# lightmeter_proto3.net
KiCad netlist of a schematic drawn in EAGLE
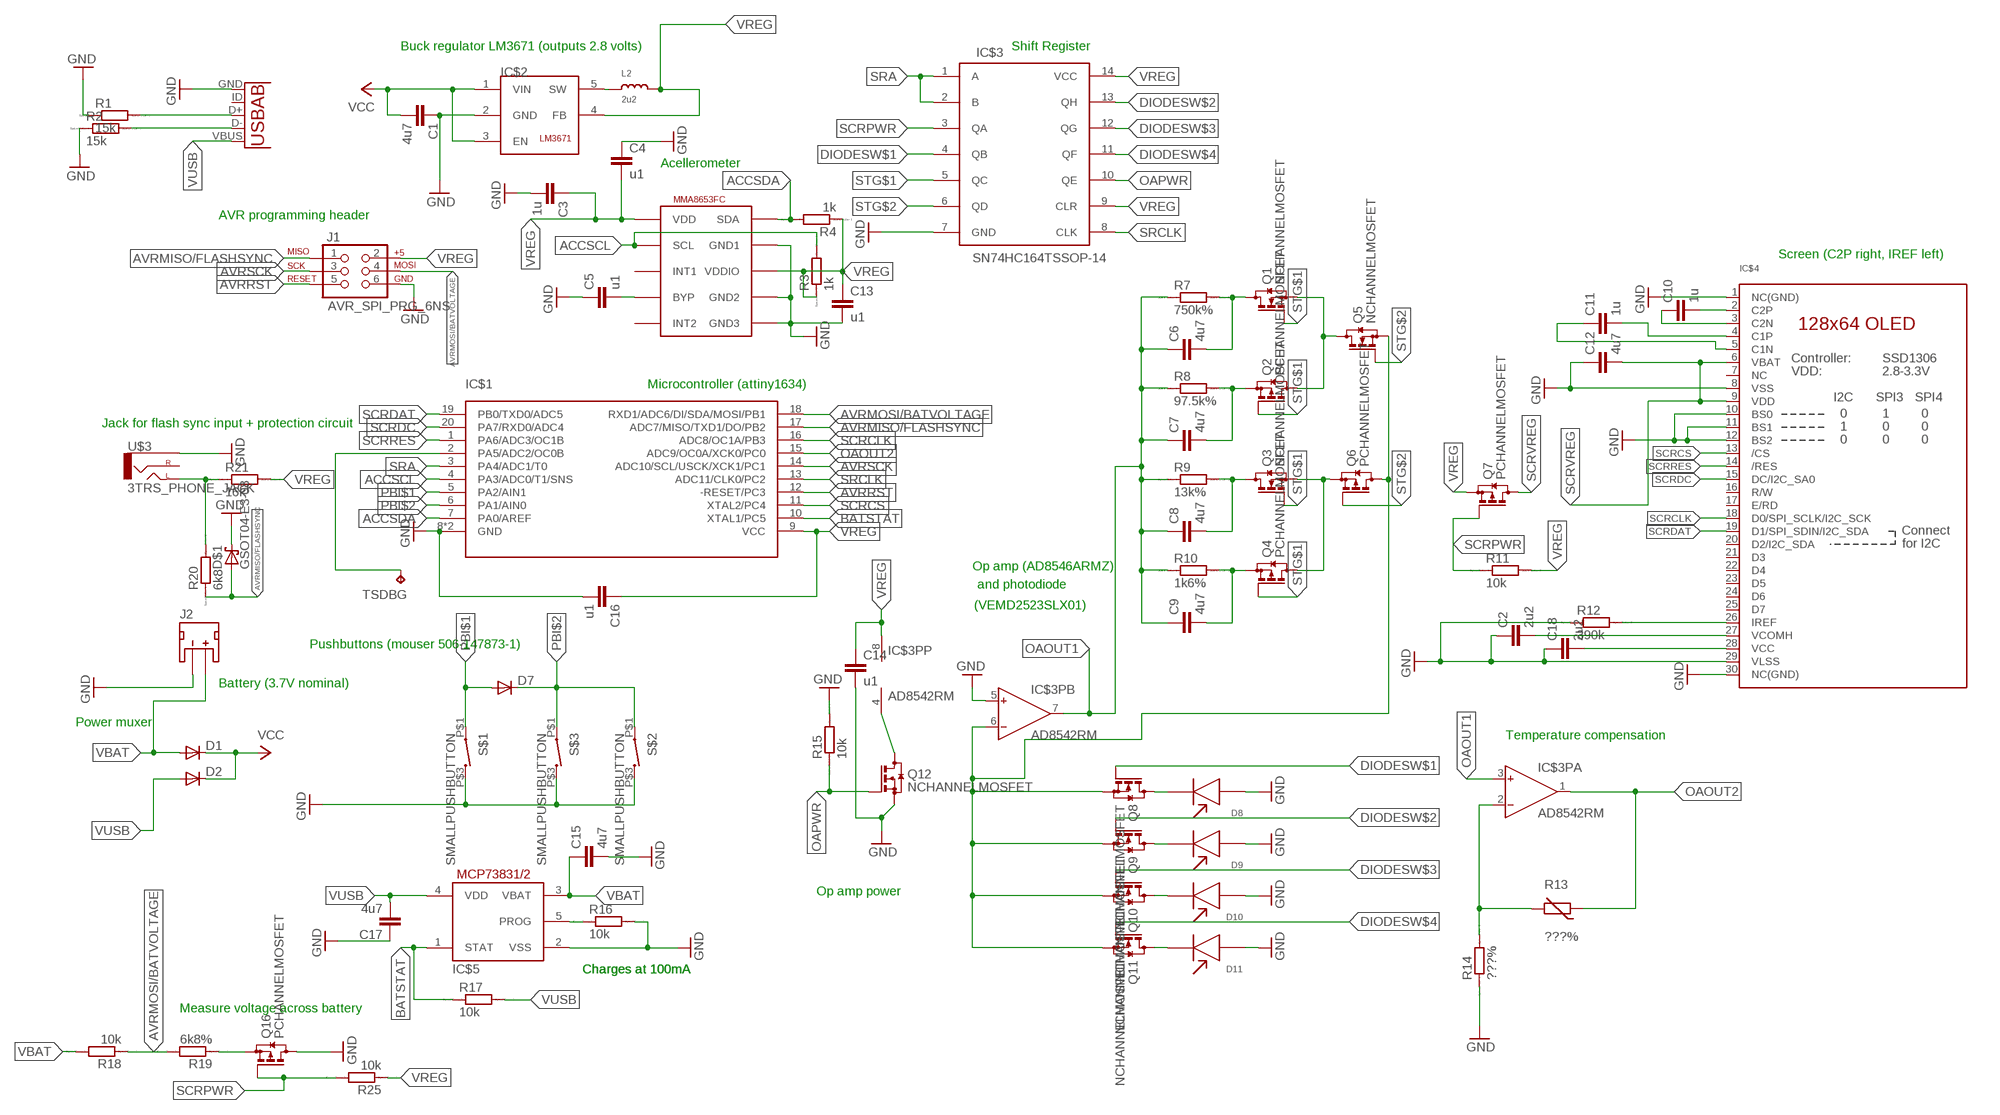
[diagram p0: schematic, sheet 1]

(export (version "E")
  (design (tool "Eeschema 10.0.6"))
  (components
    (comp (ref "C1")
      (value "4u7")
      (footprint "eagle-import:C0402")
      (libsource (lib "eagle-import") (part "C-EUC0402"))
    )
    (comp (ref "C2")
      (value "2u2")
      (footprint "eagle-import:C0402")
      (libsource (lib "eagle-import") (part "C-EUC0402"))
    )
    (comp (ref "C3")
      (value "1u")
      (footprint "eagle-import:C0402")
      (libsource (lib "eagle-import") (part "C-EUC0402"))
    )
    (comp (ref "C4")
      (value "u1")
      (footprint "eagle-import:C0402")
      (libsource (lib "eagle-import") (part "C-EUC0402"))
    )
    (comp (ref "C5")
      (value "u1")
      (footprint "eagle-import:C0402")
      (libsource (lib "eagle-import") (part "C-EUC0402"))
    )
    (comp (ref "C6")
      (value "4u7")
      (footprint "eagle-import:C0402")
      (libsource (lib "eagle-import") (part "C-EUC0402"))
    )
    (comp (ref "C7")
      (value "4u7")
      (footprint "eagle-import:C0402")
      (libsource (lib "eagle-import") (part "C-EUC0402"))
    )
    (comp (ref "C8")
      (value "4u7")
      (footprint "eagle-import:C0402")
      (libsource (lib "eagle-import") (part "C-EUC0402"))
    )
    (comp (ref "C9")
      (value "4u7")
      (footprint "eagle-import:C0402")
      (libsource (lib "eagle-import") (part "C-EUC0402"))
    )
    (comp (ref "C10")
      (value "1u")
      (footprint "eagle-import:C0402")
      (libsource (lib "eagle-import") (part "C-EUC0402"))
    )
    (comp (ref "C11")
      (value "1u")
      (footprint "eagle-import:C0402")
      (libsource (lib "eagle-import") (part "C-EUC0402"))
    )
    (comp (ref "C12")
      (value "4u7")
      (footprint "eagle-import:C0402")
      (libsource (lib "eagle-import") (part "C-EUC0402"))
    )
    (comp (ref "C13")
      (value "u1")
      (footprint "eagle-import:C0402")
      (libsource (lib "eagle-import") (part "C-EUC0402"))
    )
    (comp (ref "C14")
      (value "u1")
      (footprint "eagle-import:C0402")
      (libsource (lib "eagle-import") (part "C-EUC0402"))
    )
    (comp (ref "C15")
      (value "4u7")
      (footprint "eagle-import:C0402")
      (libsource (lib "eagle-import") (part "C-EUC0402"))
    )
    (comp (ref "C16")
      (value "u1")
      (footprint "eagle-import:C0402")
      (libsource (lib "eagle-import") (part "C-EUC0402"))
    )
    (comp (ref "C17")
      (value "4u7")
      (footprint "eagle-import:C0402")
      (libsource (lib "eagle-import") (part "C-EUC0402"))
    )
    (comp (ref "C18")
      (value "2u2")
      (footprint "eagle-import:C0402")
      (libsource (lib "eagle-import") (part "C-EUC0402"))
    )
    (comp (ref "D$1")
      (value "GSOT04-E3-08")
      (footprint "eagle-import:SOT23")
      (libsource (lib "eagle-import") (part "GSOT04-E3-08"))
    )
    (comp (ref "D1")
      (value "DIODE-SOD323-W")
      (footprint "eagle-import:SOD323-W")
      (libsource (lib "eagle-import") (part "DIODE-SOD323-W"))
    )
    (comp (ref "D2")
      (value "DIODE-SOD323-W")
      (footprint "eagle-import:SOD323-W")
      (libsource (lib "eagle-import") (part "DIODE-SOD323-W"))
    )
    (comp (ref "D7")
      (value "DIODE-SOD323-W")
      (footprint "eagle-import:SOD323-W")
      (libsource (lib "eagle-import") (part "DIODE-SOD323-W"))
    )
    (comp (ref "D8")
      (value "VEMD2523SLX01")
      (footprint "eagle-import:VEMD2523SLX01")
      (libsource (lib "eagle-import") (part "VEMD2523SLX01"))
    )
    (comp (ref "D9")
      (value "VEMD2523SLX01")
      (footprint "eagle-import:VEMD2523SLX01")
      (libsource (lib "eagle-import") (part "VEMD2523SLX01"))
    )
    (comp (ref "D10")
      (value "VEMD2523SLX01")
      (footprint "eagle-import:VEMD2523SLX01")
      (libsource (lib "eagle-import") (part "VEMD2523SLX01"))
    )
    (comp (ref "D11")
      (value "VEMD2523SLX01")
      (footprint "eagle-import:VEMD2523SLX01")
      (libsource (lib "eagle-import") (part "VEMD2523SLX01"))
    )
    (comp (ref "IC$1")
      (value "ATTINY1634MLF20")
      (footprint "eagle-import:MLF20")
      (libsource (lib "eagle-import") (part "ATTINY1634MLF20"))
    )
    (comp (ref "IC$2")
      (value "LM3671")
      (footprint "eagle-import:SOT23-5")
      (libsource (lib "eagle-import") (part "LM3671"))
    )
    (comp (ref "IC$3")
      (value "SN74HC164TSSOP-14")
      (footprint "eagle-import:TSSOP14")
      (libsource (lib "eagle-import") (part "SN74HC164TSSOP-14"))
    )
    (comp (ref "IC$3P")
      (value "AD8542RM")
      (footprint "eagle-import:MSOP08")
      (fields (field (name "MPN") "AD8542ARZ"))
      (libsource (lib "eagle-import") (part "AD8542RM"))
    )
    (comp (ref "IC$4")
      (value "DISP_OLED_UG-2864HSWEG010.96\"")
      (footprint "eagle-import:UG-2864HSWEG01_0.96IN_WRAPAROUND")
      (libsource (lib "eagle-import") (part "DISP_OLED_UG-2864HSWEG010.96{dblquote}"))
    )
    (comp (ref "IC$5")
      (value "MCP73831/OT")
      (footprint "eagle-import:SOT23-5L")
      (libsource (lib "eagle-import") (part "MCP73831/OT"))
    )
    (comp (ref "IC$6")
      (value "MMA8653")
      (footprint "eagle-import:DFN-10")
      (libsource (lib "eagle-import") (part "MMA8653"))
    )
    (comp (ref "J1")
      (value "AVR_SPI_PRG_6NS")
      (footprint "eagle-import:2X3-NS")
      (libsource (lib "eagle-import") (part "AVR_SPI_PRG_6NS"))
    )
    (comp (ref "J2")
      (value "JST_2MM_MALE")
      (footprint "eagle-import:JST-2-SMD")
      (libsource (lib "eagle-import") (part "JST_2MM_MALE"))
    )
    (comp (ref "L2")
      (value "2u2")
      (footprint "eagle-import:_0603")
      (libsource (lib "eagle-import") (part "INDUCTOR_0603"))
    )
    (comp (ref "Q1")
      (value "NCHANNELMOSFET")
      (footprint "eagle-import:SOT-416-3")
      (libsource (lib "eagle-import") (part "NCHANNELMOSFET"))
    )
    (comp (ref "Q2")
      (value "PCHANNELMOSFET")
      (footprint "eagle-import:SOT-416-3")
      (libsource (lib "eagle-import") (part "PCHANNELMOSFET"))
    )
    (comp (ref "Q3")
      (value "NCHANNELMOSFET")
      (footprint "eagle-import:SOT-416-3")
      (libsource (lib "eagle-import") (part "NCHANNELMOSFET"))
    )
    (comp (ref "Q4")
      (value "PCHANNELMOSFET")
      (footprint "eagle-import:SOT-416-3")
      (libsource (lib "eagle-import") (part "PCHANNELMOSFET"))
    )
    (comp (ref "Q5")
      (value "NCHANNELMOSFET")
      (footprint "eagle-import:SOT-416-3")
      (libsource (lib "eagle-import") (part "NCHANNELMOSFET"))
    )
    (comp (ref "Q6")
      (value "PCHANNELMOSFET")
      (footprint "eagle-import:SOT-416-3")
      (libsource (lib "eagle-import") (part "PCHANNELMOSFET"))
    )
    (comp (ref "Q7")
      (value "PCHANNELMOSFET")
      (footprint "eagle-import:SOT-416-3")
      (libsource (lib "eagle-import") (part "PCHANNELMOSFET"))
    )
    (comp (ref "Q8")
      (value "NCHANNELMOSFET")
      (footprint "eagle-import:SOT-416-3")
      (libsource (lib "eagle-import") (part "NCHANNELMOSFET"))
    )
    (comp (ref "Q9")
      (value "NCHANNELMOSFET")
      (footprint "eagle-import:SOT-416-3")
      (libsource (lib "eagle-import") (part "NCHANNELMOSFET"))
    )
    (comp (ref "Q10")
      (value "NCHANNELMOSFET")
      (footprint "eagle-import:SOT-416-3")
      (libsource (lib "eagle-import") (part "NCHANNELMOSFET"))
    )
    (comp (ref "Q11")
      (value "NCHANNELMOSFET")
      (footprint "eagle-import:SOT-416-3")
      (libsource (lib "eagle-import") (part "NCHANNELMOSFET"))
    )
    (comp (ref "Q12")
      (value "NCHANNELMOSFET")
      (footprint "eagle-import:SOT-416-3")
      (libsource (lib "eagle-import") (part "NCHANNELMOSFET"))
    )
    (comp (ref "Q16")
      (value "PCHANNELMOSFET")
      (footprint "eagle-import:SOT-416-3")
      (libsource (lib "eagle-import") (part "PCHANNELMOSFET"))
    )
    (comp (ref "R1")
      (value "15k")
      (footprint "eagle-import:R0402")
      (libsource (lib "eagle-import") (part "R-EU_R0402"))
    )
    (comp (ref "R2")
      (value "15k")
      (footprint "eagle-import:R0402")
      (libsource (lib "eagle-import") (part "R-EU_R0402"))
    )
    (comp (ref "R3")
      (value "1k")
      (footprint "eagle-import:R0402")
      (libsource (lib "eagle-import") (part "R-EU_R0402"))
    )
    (comp (ref "R4")
      (value "1k")
      (footprint "eagle-import:R0402")
      (libsource (lib "eagle-import") (part "R-EU_R0402"))
    )
    (comp (ref "R7")
      (value "750k%")
      (footprint "eagle-import:R0402")
      (libsource (lib "eagle-import") (part "R-EU_R0402"))
    )
    (comp (ref "R8")
      (value "97.5k%")
      (footprint "eagle-import:R0402")
      (libsource (lib "eagle-import") (part "R-EU_R0402"))
    )
    (comp (ref "R9")
      (value "13k%")
      (footprint "eagle-import:R0402")
      (libsource (lib "eagle-import") (part "R-EU_R0402"))
    )
    (comp (ref "R10")
      (value "1k6%")
      (footprint "eagle-import:R0402")
      (libsource (lib "eagle-import") (part "R-EU_R0402"))
    )
    (comp (ref "R11")
      (value "10k")
      (footprint "eagle-import:R0402")
      (libsource (lib "eagle-import") (part "R-EU_R0402"))
    )
    (comp (ref "R12")
      (value "390k")
      (footprint "eagle-import:R0402")
      (libsource (lib "eagle-import") (part "R-EU_R0402"))
    )
    (comp (ref "R13")
      (value "???%")
      (footprint "eagle-import:R0402")
      (libsource (lib "eagle-import") (part "THERMISTORR0402"))
    )
    (comp (ref "R14")
      (value "???%")
      (footprint "eagle-import:R0402")
      (libsource (lib "eagle-import") (part "R-EU_R0402"))
    )
    (comp (ref "R15")
      (value "10k")
      (footprint "eagle-import:R0402")
      (libsource (lib "eagle-import") (part "R-EU_R0402"))
    )
    (comp (ref "R16")
      (value "10k")
      (footprint "eagle-import:R0402")
      (libsource (lib "eagle-import") (part "R-EU_R0402"))
    )
    (comp (ref "R17")
      (value "10k")
      (footprint "eagle-import:R0402")
      (libsource (lib "eagle-import") (part "R-EU_R0402"))
    )
    (comp (ref "R18")
      (value "10k")
      (footprint "eagle-import:R0402")
      (libsource (lib "eagle-import") (part "R-EU_R0402"))
    )
    (comp (ref "R19")
      (value "6k8%")
      (footprint "eagle-import:R0402")
      (libsource (lib "eagle-import") (part "R-EU_R0402"))
    )
    (comp (ref "R20")
      (value "6k8")
      (footprint "eagle-import:R0402")
      (libsource (lib "eagle-import") (part "R-EU_R0402"))
    )
    (comp (ref "R21")
      (value "16k")
      (footprint "eagle-import:R0402")
      (libsource (lib "eagle-import") (part "R-EU_R0402"))
    )
    (comp (ref "R25")
      (value "10k")
      (footprint "eagle-import:R0402")
      (libsource (lib "eagle-import") (part "R-EU_R0402"))
    )
    (comp (ref "S$1")
      (value "SMALLPUSHBUTTON")
      (footprint "eagle-import:BUTTON")
      (libsource (lib "eagle-import") (part "SMALLPUSHBUTTON"))
    )
    (comp (ref "S$2")
      (value "SMALLPUSHBUTTON")
      (footprint "eagle-import:BUTTON")
      (libsource (lib "eagle-import") (part "SMALLPUSHBUTTON"))
    )
    (comp (ref "S$3")
      (value "SMALLPUSHBUTTON")
      (footprint "eagle-import:BUTTON")
      (libsource (lib "eagle-import") (part "SMALLPUSHBUTTON"))
    )
    (comp (ref "TSDBG")
      (value "TPPAD1-13")
      (footprint "eagle-import:P1-13")
      (libsource (lib "eagle-import") (part "TPPAD1-13"))
    )
    (comp (ref "U$3")
      (value "3TRS_PHONE_JACK")
      (footprint "eagle-import:3TRS-SMD")
      (libsource (lib "eagle-import") (part "3TRS_PHONE_JACK"))
    )
    (comp (ref "U1")
      (value "USB-AB")
      (footprint "eagle-import:USB-AB-MICRO")
      (libsource (lib "eagle-import") (part "USB-AB"))
    )
  )
  (nets
    (net (code "1") (name "ACCSCL") (class "Default")
      (node (ref "IC$1") (pin "4") (pinfunction "PA3/ADC0/T1/SNS_4") (pintype "bidirectional"))
      (node (ref "IC$6") (pin "P$2") (pinfunction "SCL_P$2") (pintype "bidirectional"))
      (node (ref "R3") (pin "2") (pinfunction "2_2") (pintype "passive"))
    )
    (net (code "2") (name "ACCSDA") (class "Default")
      (node (ref "IC$1") (pin "7") (pinfunction "PA0/AREF_7") (pintype "bidirectional"))
      (node (ref "IC$6") (pin "P$10") (pinfunction "SDA_P$10") (pintype "bidirectional"))
      (node (ref "R4") (pin "2") (pinfunction "2_2") (pintype "passive"))
    )
    (net (code "3") (name "AVRMISO{slash}FLASHSYNC") (class "Default")
      (node (ref "D$1") (pin "1") (pinfunction "A_1") (pintype "passive"))
      (node (ref "IC$1") (pin "17") (pinfunction "ADC7/MISO/TXD1/DO/PB2_17") (pintype "bidirectional"))
      (node (ref "J1") (pin "1") (pinfunction "1_1") (pintype "passive"))
      (node (ref "R20") (pin "1") (pinfunction "1_1") (pintype "passive"))
    )
    (net (code "4") (name "AVRMOSI{slash}BATVOLTAGE") (class "Default")
      (node (ref "IC$1") (pin "18") (pinfunction "RXD1/ADC6/DI/SDA/MOSI/PB1_18") (pintype "bidirectional"))
      (node (ref "J1") (pin "4") (pinfunction "4_4") (pintype "passive"))
      (node (ref "R18") (pin "1") (pinfunction "1_1") (pintype "passive"))
      (node (ref "R19") (pin "2") (pinfunction "2_2") (pintype "passive"))
    )
    (net (code "5") (name "AVRRST") (class "Default")
      (node (ref "IC$1") (pin "12") (pinfunction "-RESET/PC3_12") (pintype "bidirectional"))
      (node (ref "J1") (pin "5") (pinfunction "5_5") (pintype "passive"))
    )
    (net (code "6") (name "AVRSCK") (class "Default")
      (node (ref "IC$1") (pin "14") (pinfunction "ADC10/SCL/USCK/XCK1/PC1_14") (pintype "bidirectional"))
      (node (ref "J1") (pin "3") (pinfunction "3_3") (pintype "passive"))
    )
    (net (code "7") (name "BATSTAT") (class "Default")
      (node (ref "IC$1") (pin "10") (pinfunction "XTAL1/PC5_10") (pintype "bidirectional"))
      (node (ref "IC$5") (pin "1") (pinfunction "STAT_1") (pintype "output"))
      (node (ref "R17") (pin "1") (pinfunction "1_1") (pintype "passive"))
    )
    (net (code "8") (name "DIODESW$1") (class "Default")
      (node (ref "IC$3") (pin "4") (pinfunction "QB_4") (pintype "bidirectional"))
      (node (ref "Q8") (pin "P$1") (pinfunction "G_P$1") (pintype "passive"))
    )
    (net (code "9") (name "DIODESW$2") (class "Default")
      (node (ref "IC$3") (pin "13") (pinfunction "QH_13") (pintype "bidirectional"))
      (node (ref "Q9") (pin "P$1") (pinfunction "G_P$1") (pintype "passive"))
    )
    (net (code "10") (name "DIODESW$3") (class "Default")
      (node (ref "IC$3") (pin "12") (pinfunction "QG_12") (pintype "bidirectional"))
      (node (ref "Q10") (pin "P$1") (pinfunction "G_P$1") (pintype "passive"))
    )
    (net (code "11") (name "DIODESW$4") (class "Default")
      (node (ref "IC$3") (pin "11") (pinfunction "QF_11") (pintype "bidirectional"))
      (node (ref "Q11") (pin "P$1") (pinfunction "G_P$1") (pintype "passive"))
    )
    (net (code "12") (name "GND") (class "Default")
      (node (ref "C1") (pin "1") (pinfunction "1_1") (pintype "passive"))
      (node (ref "C12") (pin "1") (pinfunction "1_1") (pintype "passive"))
      (node (ref "C13") (pin "2") (pinfunction "2_2") (pintype "passive"))
      (node (ref "C14") (pin "2") (pinfunction "2_2") (pintype "passive"))
      (node (ref "C15") (pin "2") (pinfunction "2_2") (pintype "passive"))
      (node (ref "C16") (pin "2") (pinfunction "2_2") (pintype "passive"))
      (node (ref "C17") (pin "1") (pinfunction "1_1") (pintype "passive"))
      (node (ref "C18") (pin "1") (pinfunction "1_1") (pintype "passive"))
      (node (ref "C2") (pin "1") (pinfunction "1_1") (pintype "passive"))
      (node (ref "C3") (pin "2") (pinfunction "2_2") (pintype "passive"))
      (node (ref "C4") (pin "1") (pinfunction "1_1") (pintype "passive"))
      (node (ref "C5") (pin "1") (pinfunction "1_1") (pintype "passive"))
      (node (ref "D$1") (pin "3") (pinfunction "C_3") (pintype "passive"))
      (node (ref "D10") (pin "P$1") (pinfunction "P$1_P$1") (pintype "bidirectional"))
      (node (ref "D11") (pin "P$1") (pinfunction "P$1_P$1") (pintype "bidirectional"))
      (node (ref "D8") (pin "P$1") (pinfunction "P$1_P$1") (pintype "bidirectional"))
      (node (ref "D9") (pin "P$1") (pinfunction "P$1_P$1") (pintype "bidirectional"))
      (node (ref "IC$1") (pin "8") (pinfunction "GND_8") (pintype "power_in"))
      (node (ref "IC$1") (pin "GND") (pinfunction "GND_GND") (pintype "power_in"))
      (node (ref "IC$2") (pin "2") (pinfunction "GND_2") (pintype "bidirectional"))
      (node (ref "IC$3") (pin "7") (pinfunction "GND_7") (pintype "bidirectional"))
      (node (ref "IC$3P") (pin "5") (pinfunction "IN+_5") (pintype "input"))
      (node (ref "IC$4") (pin "1") (pinfunction "NC(GND)_1") (pintype "input"))
      (node (ref "IC$4") (pin "10") (pinfunction "BS0_10") (pintype "input"))
      (node (ref "IC$4") (pin "11") (pinfunction "BS1_11") (pintype "input"))
      (node (ref "IC$4") (pin "12") (pinfunction "BS2_12") (pintype "input"))
      (node (ref "IC$4") (pin "29") (pinfunction "VLSS_29") (pintype "power_in"))
      (node (ref "IC$4") (pin "30") (pinfunction "NC(GND)_30") (pintype "input"))
      (node (ref "IC$4") (pin "8") (pinfunction "VSS_8") (pintype "power_in"))
      (node (ref "IC$5") (pin "2") (pinfunction "VSS_2") (pintype "power_in"))
      (node (ref "IC$6") (pin "P$6") (pinfunction "GND3_P$6") (pintype "bidirectional"))
      (node (ref "IC$6") (pin "P$7") (pinfunction "GND2_P$7") (pintype "bidirectional"))
      (node (ref "IC$6") (pin "P$9") (pinfunction "GND1_P$9") (pintype "bidirectional"))
      (node (ref "J1") (pin "6") (pinfunction "6_6") (pintype "passive"))
      (node (ref "J2") (pin "1") (pinfunction "-_1") (pintype "bidirectional"))
      (node (ref "Q12") (pin "P$2") (pinfunction "S_P$2") (pintype "passive"))
      (node (ref "Q16") (pin "P$3") (pinfunction "D_P$3") (pintype "passive"))
      (node (ref "R1") (pin "1") (pinfunction "1_1") (pintype "passive"))
      (node (ref "R12") (pin "1") (pinfunction "1_1") (pintype "passive"))
      (node (ref "R14") (pin "1") (pinfunction "1_1") (pintype "passive"))
      (node (ref "R15") (pin "2") (pinfunction "2_2") (pintype "passive"))
      (node (ref "R16") (pin "2") (pinfunction "2_2") (pintype "passive"))
      (node (ref "R2") (pin "1") (pinfunction "1_1") (pintype "passive"))
      (node (ref "S$1") (pin "P$3") (pinfunction "2_P$3") (pintype "passive"))
      (node (ref "S$2") (pin "P$3") (pinfunction "2_P$3") (pintype "passive"))
      (node (ref "S$3") (pin "P$3") (pinfunction "2_P$3") (pintype "passive"))
      (node (ref "U$3") (pin "P$1") (pinfunction "SLEEVE_P$1") (pintype "bidirectional"))
      (node (ref "U1") (pin "GND") (pinfunction "GND_GND") (pintype "bidirectional"))
    )
    (net (code "13") (name "Net-(IC$1-PA5{slash}ADC2{slash}OC0B)") (class "Default")
      (node (ref "IC$1") (pin "2") (pinfunction "PA5/ADC2/OC0B_2") (pintype "bidirectional"))
      (node (ref "TSDBG") (pin "TP") (pinfunction "TP_TP") (pintype "input"))
    )
    (net (code "14") (name "Net-(IC$2-SW)") (class "Default")
      (node (ref "IC$2") (pin "5") (pinfunction "SW_5") (pintype "bidirectional"))
      (node (ref "L2") (pin "1") (pinfunction "1_1") (pintype "passive"))
    )
    (net (code "15") (name "Net-(IC$3PA-IN-)") (class "Default")
      (node (ref "IC$3P") (pin "2") (pinfunction "IN-_2") (pintype "input"))
      (node (ref "R13") (pin "2") (pinfunction "2_2") (pintype "passive"))
      (node (ref "R14") (pin "2") (pinfunction "2_2") (pintype "passive"))
    )
    (net (code "16") (name "Net-(IC$3PB-IN-)") (class "Default")
      (node (ref "IC$3P") (pin "6") (pinfunction "IN-_6") (pintype "input"))
      (node (ref "Q10") (pin "P$2") (pinfunction "S_P$2") (pintype "passive"))
      (node (ref "Q11") (pin "P$2") (pinfunction "S_P$2") (pintype "passive"))
      (node (ref "Q5") (pin "P$2") (pinfunction "S_P$2") (pintype "passive"))
      (node (ref "Q6") (pin "P$3") (pinfunction "D_P$3") (pintype "passive"))
      (node (ref "Q8") (pin "P$2") (pinfunction "S_P$2") (pintype "passive"))
      (node (ref "Q9") (pin "P$2") (pinfunction "S_P$2") (pintype "passive"))
    )
    (net (code "17") (name "Net-(IC$3PC-V-)") (class "Default")
      (node (ref "IC$3P") (pin "4") (pinfunction "V-_4") (pintype "power_in"))
      (node (ref "Q12") (pin "P$3") (pinfunction "D_P$3") (pintype "passive"))
    )
    (net (code "18") (name "Net-(IC$4-C1N)") (class "Default")
      (node (ref "C11") (pin "1") (pinfunction "1_1") (pintype "passive"))
      (node (ref "IC$4") (pin "5") (pinfunction "C1N_5") (pintype "input"))
    )
    (net (code "19") (name "Net-(IC$4-C1P)") (class "Default")
      (node (ref "C11") (pin "2") (pinfunction "2_2") (pintype "passive"))
      (node (ref "IC$4") (pin "4") (pinfunction "C1P_4") (pintype "input"))
    )
    (net (code "20") (name "Net-(IC$4-C2N)") (class "Default")
      (node (ref "C10") (pin "1") (pinfunction "1_1") (pintype "passive"))
      (node (ref "IC$4") (pin "3") (pinfunction "C2N_3") (pintype "input"))
    )
    (net (code "21") (name "Net-(IC$4-C2P)") (class "Default")
      (node (ref "C10") (pin "2") (pinfunction "2_2") (pintype "passive"))
      (node (ref "IC$4") (pin "2") (pinfunction "C2P_2") (pintype "input"))
    )
    (net (code "22") (name "Net-(IC$4-IREF)") (class "Default")
      (node (ref "IC$4") (pin "26") (pinfunction "IREF_26") (pintype "input"))
      (node (ref "R12") (pin "2") (pinfunction "2_2") (pintype "passive"))
    )
    (net (code "23") (name "Net-(IC$4-VCC)") (class "Default")
      (node (ref "C18") (pin "2") (pinfunction "2_2") (pintype "passive"))
      (node (ref "IC$4") (pin "28") (pinfunction "VCC_28") (pintype "power_in"))
    )
    (net (code "24") (name "Net-(IC$4-VCOMH)") (class "Default")
      (node (ref "C2") (pin "2") (pinfunction "2_2") (pintype "passive"))
      (node (ref "IC$4") (pin "27") (pinfunction "VCOMH_27") (pintype "output"))
    )
    (net (code "25") (name "Net-(IC$5-PROG)") (class "Default")
      (node (ref "IC$5") (pin "5") (pinfunction "PROG_5") (pintype "input"))
      (node (ref "R16") (pin "1") (pinfunction "1_1") (pintype "passive"))
    )
    (net (code "26") (name "Net-(IC$6-BYP)") (class "Default")
      (node (ref "C5") (pin "2") (pinfunction "2_2") (pintype "passive"))
      (node (ref "IC$6") (pin "P$4") (pinfunction "BYP_P$4") (pintype "bidirectional"))
    )
    (net (code "27") (name "Net-(Q1-D)") (class "Default")
      (node (ref "C6") (pin "2") (pinfunction "2_2") (pintype "passive"))
      (node (ref "Q1") (pin "P$3") (pinfunction "D_P$3") (pintype "passive"))
      (node (ref "R7") (pin "2") (pinfunction "2_2") (pintype "passive"))
    )
    (net (code "28") (name "Net-(Q1-S)") (class "Default")
      (node (ref "Q1") (pin "P$2") (pinfunction "S_P$2") (pintype "passive"))
      (node (ref "Q2") (pin "P$3") (pinfunction "D_P$3") (pintype "passive"))
      (node (ref "Q5") (pin "P$3") (pinfunction "D_P$3") (pintype "passive"))
    )
    (net (code "29") (name "Net-(Q2-S)") (class "Default")
      (node (ref "C7") (pin "2") (pinfunction "2_2") (pintype "passive"))
      (node (ref "Q2") (pin "P$2") (pinfunction "S_P$2") (pintype "passive"))
      (node (ref "R8") (pin "2") (pinfunction "2_2") (pintype "passive"))
    )
    (net (code "30") (name "Net-(Q3-D)") (class "Default")
      (node (ref "C8") (pin "2") (pinfunction "2_2") (pintype "passive"))
      (node (ref "Q3") (pin "P$3") (pinfunction "D_P$3") (pintype "passive"))
      (node (ref "R9") (pin "2") (pinfunction "2_2") (pintype "passive"))
    )
    (net (code "31") (name "Net-(Q3-S)") (class "Default")
      (node (ref "Q3") (pin "P$2") (pinfunction "S_P$2") (pintype "passive"))
      (node (ref "Q4") (pin "P$3") (pinfunction "D_P$3") (pintype "passive"))
      (node (ref "Q6") (pin "P$2") (pinfunction "S_P$2") (pintype "passive"))
    )
    (net (code "32") (name "Net-(Q4-S)") (class "Default")
      (node (ref "C9") (pin "2") (pinfunction "2_2") (pintype "passive"))
      (node (ref "Q4") (pin "P$2") (pinfunction "S_P$2") (pintype "passive"))
      (node (ref "R10") (pin "2") (pinfunction "2_2") (pintype "passive"))
    )
    (net (code "33") (name "Net-(Q8-D)") (class "Default")
      (node (ref "D8") (pin "P$2") (pinfunction "P$2_P$2") (pintype "bidirectional"))
      (node (ref "Q8") (pin "P$3") (pinfunction "D_P$3") (pintype "passive"))
    )
    (net (code "34") (name "Net-(Q9-D)") (class "Default")
      (node (ref "D9") (pin "P$2") (pinfunction "P$2_P$2") (pintype "bidirectional"))
      (node (ref "Q9") (pin "P$3") (pinfunction "D_P$3") (pintype "passive"))
    )
    (net (code "35") (name "Net-(Q10-D)") (class "Default")
      (node (ref "D10") (pin "P$2") (pinfunction "P$2_P$2") (pintype "bidirectional"))
      (node (ref "Q10") (pin "P$3") (pinfunction "D_P$3") (pintype "passive"))
    )
    (net (code "36") (name "Net-(Q11-D)") (class "Default")
      (node (ref "D11") (pin "P$2") (pinfunction "P$2_P$2") (pintype "bidirectional"))
      (node (ref "Q11") (pin "P$3") (pinfunction "D_P$3") (pintype "passive"))
    )
    (net (code "37") (name "Net-(Q16-S)") (class "Default")
      (node (ref "Q16") (pin "P$2") (pinfunction "S_P$2") (pintype "passive"))
      (node (ref "R19") (pin "1") (pinfunction "1_1") (pintype "passive"))
    )
    (net (code "38") (name "Net-(R1-Pad2)") (class "Default")
      (node (ref "R1") (pin "2") (pinfunction "2_2") (pintype "passive"))
      (node (ref "U1") (pin "D+") (pinfunction "D+_D+") (pintype "bidirectional"))
    )
    (net (code "39") (name "Net-(R2-Pad2)") (class "Default")
      (node (ref "R2") (pin "2") (pinfunction "2_2") (pintype "passive"))
      (node (ref "U1") (pin "D-") (pinfunction "D-_D-") (pintype "bidirectional"))
    )
    (net (code "40") (name "Net-(U$3-LEFT)") (class "Default")
      (node (ref "R20") (pin "2") (pinfunction "2_2") (pintype "passive"))
      (node (ref "R21") (pin "1") (pinfunction "1_1") (pintype "passive"))
      (node (ref "U$3") (pin "P$3") (pinfunction "LEFT_P$3") (pintype "bidirectional"))
    )
    (net (code "41") (name "OAOUT1") (class "Default")
      (node (ref "C6") (pin "1") (pinfunction "1_1") (pintype "passive"))
      (node (ref "C7") (pin "1") (pinfunction "1_1") (pintype "passive"))
      (node (ref "C8") (pin "1") (pinfunction "1_1") (pintype "passive"))
      (node (ref "C9") (pin "1") (pinfunction "1_1") (pintype "passive"))
      (node (ref "IC$3P") (pin "3") (pinfunction "IN+_3") (pintype "input"))
      (node (ref "IC$3P") (pin "7") (pinfunction "OUT_7") (pintype "output"))
      (node (ref "R10") (pin "1") (pinfunction "1_1") (pintype "passive"))
      (node (ref "R7") (pin "1") (pinfunction "1_1") (pintype "passive"))
      (node (ref "R8") (pin "1") (pinfunction "1_1") (pintype "passive"))
      (node (ref "R9") (pin "1") (pinfunction "1_1") (pintype "passive"))
    )
    (net (code "42") (name "OAOUT2") (class "Default")
      (node (ref "IC$1") (pin "15") (pinfunction "ADC9/OC0A/XCK0/PC0_15") (pintype "bidirectional"))
      (node (ref "IC$3P") (pin "1") (pinfunction "OUT_1") (pintype "output"))
      (node (ref "R13") (pin "1") (pinfunction "1_1") (pintype "passive"))
    )
    (net (code "43") (name "OAPWR") (class "Default")
      (node (ref "IC$3") (pin "10") (pinfunction "QE_10") (pintype "bidirectional"))
      (node (ref "Q12") (pin "P$1") (pinfunction "G_P$1") (pintype "passive"))
      (node (ref "R15") (pin "1") (pinfunction "1_1") (pintype "passive"))
    )
    (net (code "44") (name "PBI$1") (class "Default")
      (node (ref "D7") (pin "A") (pinfunction "A_A") (pintype "passive"))
      (node (ref "IC$1") (pin "5") (pinfunction "PA2/AIN1_5") (pintype "bidirectional"))
      (node (ref "S$1") (pin "P$1") (pinfunction "1_P$1") (pintype "passive"))
    )
    (net (code "45") (name "PBI$2") (class "Default")
      (node (ref "D7") (pin "C") (pinfunction "C_C") (pintype "passive"))
      (node (ref "IC$1") (pin "6") (pinfunction "PA1/AIN0_6") (pintype "bidirectional"))
      (node (ref "S$2") (pin "P$1") (pinfunction "1_P$1") (pintype "passive"))
      (node (ref "S$3") (pin "P$1") (pinfunction "1_P$1") (pintype "passive"))
    )
    (net (code "46") (name "SCRCLK") (class "Default")
      (node (ref "IC$1") (pin "16") (pinfunction "ADC8/OC1A/PB3_16") (pintype "bidirectional"))
      (node (ref "IC$4") (pin "18") (pinfunction "D0/SPI_SCLK/I2C_SCK_18") (pintype "bidirectional"))
    )
    (net (code "47") (name "SCRCS") (class "Default")
      (node (ref "IC$1") (pin "11") (pinfunction "XTAL2/PC4_11") (pintype "bidirectional"))
      (node (ref "IC$4") (pin "13") (pinfunction "/CS_13") (pintype "input"))
    )
    (net (code "48") (name "SCRDAT") (class "Default")
      (node (ref "IC$1") (pin "19") (pinfunction "PB0/TXD0/ADC5_19") (pintype "bidirectional"))
      (node (ref "IC$4") (pin "19") (pinfunction "D1/SPI_SDIN/I2C_SDA_19") (pintype "bidirectional"))
    )
    (net (code "49") (name "SCRDC") (class "Default")
      (node (ref "IC$1") (pin "20") (pinfunction "PA7/RXD0/ADC4_20") (pintype "bidirectional"))
      (node (ref "IC$4") (pin "15") (pinfunction "DC/I2C_SA0_15") (pintype "input"))
    )
    (net (code "50") (name "SCRPWR") (class "Default")
      (node (ref "IC$3") (pin "3") (pinfunction "QA_3") (pintype "bidirectional"))
      (node (ref "Q16") (pin "P$1") (pinfunction "G_P$1") (pintype "passive"))
      (node (ref "Q7") (pin "P$1") (pinfunction "G_P$1") (pintype "passive"))
      (node (ref "R11") (pin "1") (pinfunction "1_1") (pintype "passive"))
      (node (ref "R25") (pin "2") (pinfunction "2_2") (pintype "passive"))
    )
    (net (code "51") (name "SCRRES") (class "Default")
      (node (ref "IC$1") (pin "1") (pinfunction "PA6/ADC3/OC1B_1") (pintype "bidirectional"))
      (node (ref "IC$4") (pin "14") (pinfunction "/RES_14") (pintype "input"))
    )
    (net (code "52") (name "SCRVREG") (class "Default")
      (node (ref "C12") (pin "2") (pinfunction "2_2") (pintype "passive"))
      (node (ref "IC$4") (pin "6") (pinfunction "VBAT_6") (pintype "input"))
      (node (ref "IC$4") (pin "9") (pinfunction "VDD_9") (pintype "power_in"))
      (node (ref "Q7") (pin "P$3") (pinfunction "D_P$3") (pintype "passive"))
    )
    (net (code "53") (name "SRA") (class "Default")
      (node (ref "IC$1") (pin "3") (pinfunction "PA4/ADC1/T0_3") (pintype "bidirectional"))
      (node (ref "IC$3") (pin "1") (pinfunction "A_1") (pintype "bidirectional"))
      (node (ref "IC$3") (pin "2") (pinfunction "B_2") (pintype "bidirectional"))
    )
    (net (code "54") (name "SRCLK") (class "Default")
      (node (ref "IC$1") (pin "13") (pinfunction "ADC11/CLK0/PC2_13") (pintype "bidirectional"))
      (node (ref "IC$3") (pin "8") (pinfunction "CLK_8") (pintype "bidirectional"))
    )
    (net (code "55") (name "STG$1") (class "Default")
      (node (ref "IC$3") (pin "5") (pinfunction "QC_5") (pintype "bidirectional"))
      (node (ref "Q1") (pin "P$1") (pinfunction "G_P$1") (pintype "passive"))
      (node (ref "Q2") (pin "P$1") (pinfunction "G_P$1") (pintype "passive"))
      (node (ref "Q3") (pin "P$1") (pinfunction "G_P$1") (pintype "passive"))
      (node (ref "Q4") (pin "P$1") (pinfunction "G_P$1") (pintype "passive"))
    )
    (net (code "56") (name "STG$2") (class "Default")
      (node (ref "IC$3") (pin "6") (pinfunction "QD_6") (pintype "bidirectional"))
      (node (ref "Q5") (pin "P$1") (pinfunction "G_P$1") (pintype "passive"))
      (node (ref "Q6") (pin "P$1") (pinfunction "G_P$1") (pintype "passive"))
    )
    (net (code "57") (name "VBAT") (class "Default")
      (node (ref "C15") (pin "1") (pinfunction "1_1") (pintype "passive"))
      (node (ref "D1") (pin "A") (pinfunction "A_A") (pintype "passive"))
      (node (ref "IC$5") (pin "3") (pinfunction "VBAT_3") (pintype "bidirectional"))
      (node (ref "J2") (pin "2") (pinfunction "+_2") (pintype "bidirectional"))
      (node (ref "R18") (pin "2") (pinfunction "2_2") (pintype "passive"))
    )
    (net (code "58") (name "VCC") (class "Default")
      (node (ref "C1") (pin "2") (pinfunction "2_2") (pintype "passive"))
      (node (ref "D1") (pin "C") (pinfunction "C_C") (pintype "passive"))
      (node (ref "D2") (pin "C") (pinfunction "C_C") (pintype "passive"))
      (node (ref "IC$2") (pin "1") (pinfunction "VIN_1") (pintype "bidirectional"))
      (node (ref "IC$2") (pin "3") (pinfunction "EN_3") (pintype "bidirectional"))
    )
    (net (code "59") (name "VREG") (class "Default")
      (node (ref "C13") (pin "1") (pinfunction "1_1") (pintype "passive"))
      (node (ref "C14") (pin "1") (pinfunction "1_1") (pintype "passive"))
      (node (ref "C16") (pin "1") (pinfunction "1_1") (pintype "passive"))
      (node (ref "C3") (pin "1") (pinfunction "1_1") (pintype "passive"))
      (node (ref "C4") (pin "2") (pinfunction "2_2") (pintype "passive"))
      (node (ref "IC$1") (pin "9") (pinfunction "VCC_9") (pintype "power_in"))
      (node (ref "IC$2") (pin "4") (pinfunction "FB_4") (pintype "bidirectional"))
      (node (ref "IC$3") (pin "14") (pinfunction "VCC_14") (pintype "bidirectional"))
      (node (ref "IC$3") (pin "9") (pinfunction "CLR_9") (pintype "bidirectional"))
      (node (ref "IC$3P") (pin "8") (pinfunction "V+_8") (pintype "power_in"))
      (node (ref "IC$6") (pin "P$1") (pinfunction "VDD_P$1") (pintype "bidirectional"))
      (node (ref "IC$6") (pin "P$8") (pinfunction "VDDIO_P$8") (pintype "bidirectional"))
      (node (ref "J1") (pin "2") (pinfunction "2_2") (pintype "passive"))
      (node (ref "L2") (pin "2") (pinfunction "2_2") (pintype "passive"))
      (node (ref "Q7") (pin "P$2") (pinfunction "S_P$2") (pintype "passive"))
      (node (ref "R11") (pin "2") (pinfunction "2_2") (pintype "passive"))
      (node (ref "R21") (pin "2") (pinfunction "2_2") (pintype "passive"))
      (node (ref "R25") (pin "1") (pinfunction "1_1") (pintype "passive"))
      (node (ref "R3") (pin "1") (pinfunction "1_1") (pintype "passive"))
      (node (ref "R4") (pin "1") (pinfunction "1_1") (pintype "passive"))
    )
    (net (code "60") (name "VUSB") (class "Default")
      (node (ref "C17") (pin "2") (pinfunction "2_2") (pintype "passive"))
      (node (ref "D2") (pin "A") (pinfunction "A_A") (pintype "passive"))
      (node (ref "IC$5") (pin "4") (pinfunction "VDD_4") (pintype "power_in"))
      (node (ref "R17") (pin "2") (pinfunction "2_2") (pintype "passive"))
      (node (ref "U1") (pin "VBUS") (pinfunction "VBUS_VBUS") (pintype "bidirectional"))
    )
    (net (code "61") (name "unconnected-(IC$4-D2{slash}I2C_SDA-Pad20)") (class "Default")
      (node (ref "IC$4") (pin "20") (pinfunction "D2/I2C_SDA_20") (pintype "bidirectional"))
    )
    (net (code "62") (name "unconnected-(IC$4-D3-Pad21)") (class "Default")
      (node (ref "IC$4") (pin "21") (pinfunction "D3_21") (pintype "bidirectional"))
    )
    (net (code "63") (name "unconnected-(IC$4-D4-Pad22)") (class "Default")
      (node (ref "IC$4") (pin "22") (pinfunction "D4_22") (pintype "bidirectional"))
    )
    (net (code "64") (name "unconnected-(IC$4-D5-Pad23)") (class "Default")
      (node (ref "IC$4") (pin "23") (pinfunction "D5_23") (pintype "bidirectional"))
    )
    (net (code "65") (name "unconnected-(IC$4-D6-Pad24)") (class "Default")
      (node (ref "IC$4") (pin "24") (pinfunction "D6_24") (pintype "bidirectional"))
    )
    (net (code "66") (name "unconnected-(IC$4-D7-Pad25)") (class "Default")
      (node (ref "IC$4") (pin "25") (pinfunction "D7_25") (pintype "bidirectional"))
    )
    (net (code "67") (name "unconnected-(IC$4-E{slash}RD-Pad17)") (class "Default")
      (node (ref "IC$4") (pin "17") (pinfunction "E/RD_17") (pintype "input"))
    )
    (net (code "68") (name "unconnected-(IC$4-NC-Pad7)") (class "Default")
      (node (ref "IC$4") (pin "7") (pinfunction "NC_7") (pintype "no_connect"))
    )
    (net (code "69") (name "unconnected-(IC$4-R{slash}W-Pad16)") (class "Default")
      (node (ref "IC$4") (pin "16") (pinfunction "R/W_16") (pintype "input"))
    )
    (net (code "70") (name "unconnected-(IC$6-INT1-PadP$3)") (class "Default")
      (node (ref "IC$6") (pin "P$3") (pinfunction "INT1_P$3") (pintype "bidirectional"))
    )
    (net (code "71") (name "unconnected-(IC$6-INT2-PadP$5)") (class "Default")
      (node (ref "IC$6") (pin "P$5") (pinfunction "INT2_P$5") (pintype "bidirectional"))
    )
    (net (code "72") (name "unconnected-(J2-PAD1-PadNC1)") (class "Default")
      (node (ref "J2") (pin "NC1") (pinfunction "PAD1_NC1") (pintype "bidirectional"))
    )
    (net (code "73") (name "unconnected-(J2-PAD2-PadNC2)") (class "Default")
      (node (ref "J2") (pin "NC2") (pinfunction "PAD2_NC2") (pintype "bidirectional"))
    )
    (net (code "74") (name "unconnected-(U$3-RIGHT-PadP$2)") (class "Default")
      (node (ref "U$3") (pin "P$2") (pinfunction "RIGHT_P$2") (pintype "bidirectional"))
    )
    (net (code "75") (name "unconnected-(U1-USBID-PadID)") (class "Default")
      (node (ref "U1") (pin "ID") (pinfunction "USBID_ID") (pintype "bidirectional"))
    )
  )
)
